# 04_-_MICRO.net
KiCad netlist of a schematic drawn in Altium Designer
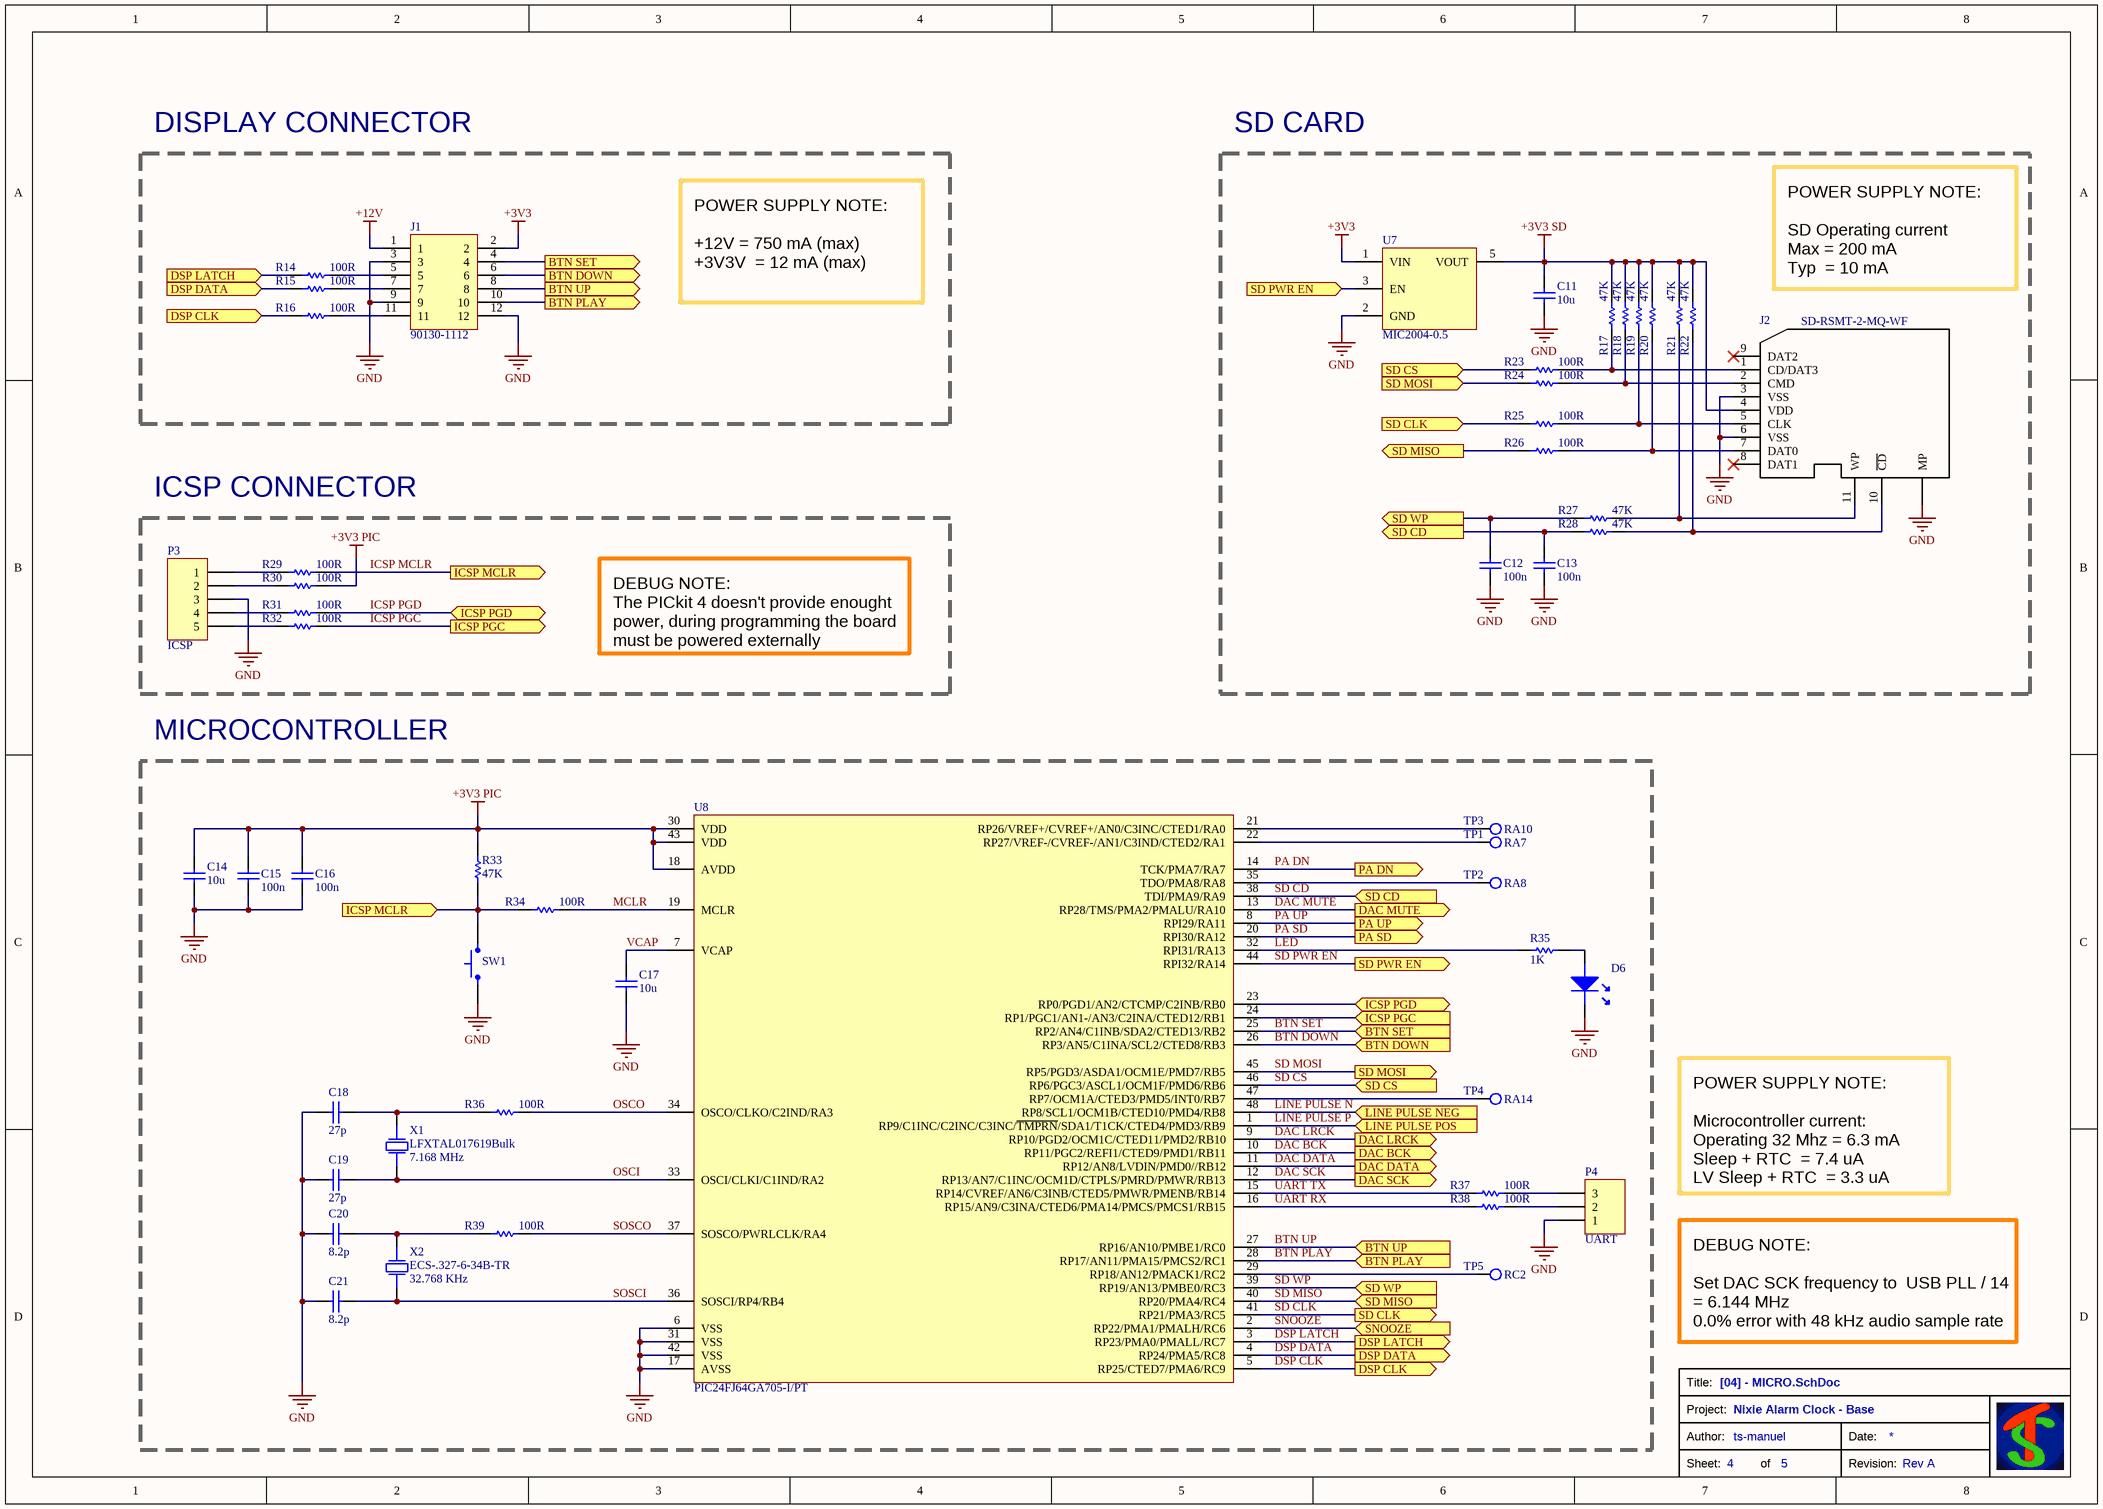
[diagram p0: [04] - MICRO.SchDoc]

(export (version "E")
  (design (tool "Eeschema 10.0.6"))
  (components
    (comp (ref "C11")
      (value "10u")
      (footprint "CAP-0805")
      (description "MLCC - SMD 25V 10uF X5R 10%")
      (fields (field (name "MANUFACTURER") "Samsung") (field (name "TOLERANCE") "10%"))
      (libsource (lib "Passives") (part "CAP-0805-10u-25V-X5R-10%"))
    )
    (comp (ref "C12")
      (value "100n")
      (footprint "CAP-0603")
      (description "MLCC - SMD 16V 100nF X7R 0603 20%")
      (fields (field (name "TOLERANCE") "20%") (field (name "MANUFACTURER") "KEMET"))
      (libsource (lib "Passives") (part "CAP-0603-100n-16V-X7R-20%"))
    )
    (comp (ref "C13")
      (value "100n")
      (footprint "CAP-0603")
      (description "MLCC - SMD 16V 100nF X7R 0603 20%")
      (fields (field (name "TOLERANCE") "20%") (field (name "MANUFACTURER") "KEMET"))
      (libsource (lib "Passives") (part "CAP-0603-100n-16V-X7R-20%"))
    )
    (comp (ref "C14")
      (value "10u")
      (footprint "CAP-0805")
      (description "MLCC - SMD 25V 10uF X5R 10%")
      (fields (field (name "MANUFACTURER") "Samsung") (field (name "TOLERANCE") "10%"))
      (libsource (lib "Passives") (part "CAP-0805-10u-25V-X5R-10%"))
    )
    (comp (ref "C15")
      (value "100n")
      (footprint "CAP-0603")
      (description "MLCC - SMD 16V 100nF X7R 0603 20%")
      (fields (field (name "TOLERANCE") "20%") (field (name "MANUFACTURER") "KEMET"))
      (libsource (lib "Passives") (part "CAP-0603-100n-16V-X7R-20%"))
    )
    (comp (ref "C16")
      (value "100n")
      (footprint "CAP-0603")
      (description "MLCC - SMD 16V 100nF X7R 0603 20%")
      (fields (field (name "TOLERANCE") "20%") (field (name "MANUFACTURER") "KEMET"))
      (libsource (lib "Passives") (part "CAP-0603-100n-16V-X7R-20%"))
    )
    (comp (ref "C17")
      (value "10u")
      (footprint "CAP-0805")
      (description "MLCC - SMD 25V 10uF X5R 10%")
      (fields (field (name "MANUFACTURER") "Samsung") (field (name "TOLERANCE") "10%"))
      (libsource (lib "Passives") (part "CAP-0805-10u-25V-X5R-10%"))
    )
    (comp (ref "C18")
      (value "27p")
      (footprint "CAP-0603")
      (description "MLCC - SMD 50V 27pF NP0 0603 5%")
      (fields (field (name "MANUFACTURER") "KEMET") (field (name "TOLERANCE") "5%"))
      (libsource (lib "Passives") (part "CAP-0603-27p-50V-NP0-5%"))
    )
    (comp (ref "C19")
      (value "27p")
      (footprint "CAP-0603")
      (description "MLCC - SMD 50V 27pF NP0 0603 5%")
      (fields (field (name "MANUFACTURER") "KEMET") (field (name "TOLERANCE") "5%"))
      (libsource (lib "Passives") (part "CAP-0603-27p-50V-NP0-5%"))
    )
    (comp (ref "C20")
      (value "8.2p")
      (footprint "CAP-0603")
      (description "MLCC - SMD 50V 8.2pF NP0 0603 5%")
      (fields (field (name "MANUFACTURER") "YAGEO") (field (name "TOLERANCE") "5%"))
      (libsource (lib "Passives") (part "CAP-0603-8p2-50V-NP0-5%"))
    )
    (comp (ref "C21")
      (value "8.2p")
      (footprint "CAP-0603")
      (description "MLCC - SMD 50V 8.2pF NP0 0603 5%")
      (fields (field (name "MANUFACTURER") "YAGEO") (field (name "TOLERANCE") "5%"))
      (libsource (lib "Passives") (part "CAP-0603-8p2-50V-NP0-5%"))
    )
    (comp (ref "D6")
      (value "150060VS75000")
      (footprint "LED-SMD-0603-1.6X0.8")
      (description "Standard LEDs - SMD WL-SMCW SMDMono TpVw Waterclr 0603 BrtGrn")
      (fields (field (name "MANUFACTURER") "Wurth Elektronik"))
      (libsource (lib "mt_local_library") (part "LED-SMD-0603-Green-150060VS75000"))
    )
    (comp (ref "J1")
      (value "90130-1112")
      (footprint "SHDR12W65P254_2X6_1758X975X1110P")
      (description "Terminali e capicorda 2.54MM CGRIDIII HDR 12P V DR SHRD TIN")
      (libsource (lib "mt_local_library") (part "HEADER-12x2-2.54-TH-90130-1112"))
    )
    (comp (ref "J2")
      (value "SD-RSMT-2-MQ-WF")
      (footprint "SD 3M SD-RSMT-2-MQ-WF")
      (description "Connettori per schede di memoria SD CARD CONNECTOR")
      (libsource (lib "mt_local_library") (part "SD-PUSH-PUSH-SD-RSMT-2-MQ-WF"))
    )
    (comp (ref "P3")
      (value "ICSP")
      (footprint "HDR1X5")
      (description "Header, 5-Pin")
      (fields (field (name "PUBLISHER") "Altium Limited"))
      (libsource (lib "Miscellaneous Connectors") (part "Header 5"))
    )
    (comp (ref "P4")
      (value "UART")
      (footprint "HDR1X3")
      (description "Header, 3-Pin")
      (fields (field (name "PUBLISHER") "Altium Limited"))
      (libsource (lib "Miscellaneous Connectors") (part "Header 3"))
    )
    (comp (ref "R14")
      (value "100R")
      (footprint "RES-0603")
      (description "Thick Film - SMD 75V 1/10W 100 ohm 0603 1%")
      (fields (field (name "MANUFACTURER") "Yageo") (field (name "TOLERANCE") "1%"))
      (libsource (lib "Passives") (part "RES-0603-100R-1/10W-1%"))
    )
    (comp (ref "R15")
      (value "100R")
      (footprint "RES-0603")
      (description "Thick Film - SMD 75V 1/10W 100 ohm 0603 1%")
      (fields (field (name "MANUFACTURER") "Yageo") (field (name "TOLERANCE") "1%"))
      (libsource (lib "Passives") (part "RES-0603-100R-1/10W-1%"))
    )
    (comp (ref "R16")
      (value "100R")
      (footprint "RES-0603")
      (description "Thick Film - SMD 75V 1/10W 100 ohm 0603 1%")
      (fields (field (name "MANUFACTURER") "Yageo") (field (name "TOLERANCE") "1%"))
      (libsource (lib "Passives") (part "RES-0603-100R-1/10W-1%"))
    )
    (comp (ref "R17")
      (value "47K")
      (footprint "RES-0603")
      (description "Thick Film - SMD 75V 1/10W 47K ohm 0603 1%")
      (fields (field (name "MANUFACTURER") "Yageo") (field (name "TOLERANCE") "1%"))
      (libsource (lib "Passives") (part "RES-0603-47K-1/10W-1%"))
    )
    (comp (ref "R18")
      (value "47K")
      (footprint "RES-0603")
      (description "Thick Film - SMD 75V 1/10W 47K ohm 0603 1%")
      (fields (field (name "MANUFACTURER") "Yageo") (field (name "TOLERANCE") "1%"))
      (libsource (lib "Passives") (part "RES-0603-47K-1/10W-1%"))
    )
    (comp (ref "R19")
      (value "47K")
      (footprint "RES-0603")
      (description "Thick Film - SMD 75V 1/10W 47K ohm 0603 1%")
      (fields (field (name "MANUFACTURER") "Yageo") (field (name "TOLERANCE") "1%"))
      (libsource (lib "Passives") (part "RES-0603-47K-1/10W-1%"))
    )
    (comp (ref "R20")
      (value "47K")
      (footprint "RES-0603")
      (description "Thick Film - SMD 75V 1/10W 47K ohm 0603 1%")
      (fields (field (name "MANUFACTURER") "Yageo") (field (name "TOLERANCE") "1%"))
      (libsource (lib "Passives") (part "RES-0603-47K-1/10W-1%"))
    )
    (comp (ref "R21")
      (value "47K")
      (footprint "RES-0603")
      (description "Thick Film - SMD 75V 1/10W 47K ohm 0603 1%")
      (fields (field (name "MANUFACTURER") "Yageo") (field (name "TOLERANCE") "1%"))
      (libsource (lib "Passives") (part "RES-0603-47K-1/10W-1%"))
    )
    (comp (ref "R22")
      (value "47K")
      (footprint "RES-0603")
      (description "Thick Film - SMD 75V 1/10W 47K ohm 0603 1%")
      (fields (field (name "MANUFACTURER") "Yageo") (field (name "TOLERANCE") "1%"))
      (libsource (lib "Passives") (part "RES-0603-47K-1/10W-1%"))
    )
    (comp (ref "R23")
      (value "100R")
      (footprint "RES-0603")
      (description "Thick Film - SMD 75V 1/10W 100 ohm 0603 1%")
      (fields (field (name "MANUFACTURER") "Yageo") (field (name "TOLERANCE") "1%"))
      (libsource (lib "Passives") (part "RES-0603-100R-1/10W-1%"))
    )
    (comp (ref "R24")
      (value "100R")
      (footprint "RES-0603")
      (description "Thick Film - SMD 75V 1/10W 100 ohm 0603 1%")
      (fields (field (name "MANUFACTURER") "Yageo") (field (name "TOLERANCE") "1%"))
      (libsource (lib "Passives") (part "RES-0603-100R-1/10W-1%"))
    )
    (comp (ref "R25")
      (value "100R")
      (footprint "RES-0603")
      (description "Thick Film - SMD 75V 1/10W 100 ohm 0603 1%")
      (fields (field (name "MANUFACTURER") "Yageo") (field (name "TOLERANCE") "1%"))
      (libsource (lib "Passives") (part "RES-0603-100R-1/10W-1%"))
    )
    (comp (ref "R26")
      (value "100R")
      (footprint "RES-0603")
      (description "Thick Film - SMD 75V 1/10W 100 ohm 0603 1%")
      (fields (field (name "MANUFACTURER") "Yageo") (field (name "TOLERANCE") "1%"))
      (libsource (lib "Passives") (part "RES-0603-100R-1/10W-1%"))
    )
    (comp (ref "R27")
      (value "47K")
      (footprint "RES-0603")
      (description "Thick Film - SMD 75V 1/10W 47K ohm 0603 1%")
      (fields (field (name "MANUFACTURER") "Yageo") (field (name "TOLERANCE") "1%"))
      (libsource (lib "Passives") (part "RES-0603-47K-1/10W-1%"))
    )
    (comp (ref "R28")
      (value "47K")
      (footprint "RES-0603")
      (description "Thick Film - SMD 75V 1/10W 47K ohm 0603 1%")
      (fields (field (name "MANUFACTURER") "Yageo") (field (name "TOLERANCE") "1%"))
      (libsource (lib "Passives") (part "RES-0603-47K-1/10W-1%"))
    )
    (comp (ref "R29")
      (value "100R")
      (footprint "RES-0603")
      (description "Thick Film - SMD 75V 1/10W 100 ohm 0603 1%")
      (fields (field (name "MANUFACTURER") "Yageo") (field (name "TOLERANCE") "1%"))
      (libsource (lib "Passives") (part "RES-0603-100R-1/10W-1%"))
    )
    (comp (ref "R30")
      (value "100R")
      (footprint "RES-0603")
      (description "Thick Film - SMD 75V 1/10W 100 ohm 0603 1%")
      (fields (field (name "MANUFACTURER") "Yageo") (field (name "TOLERANCE") "1%"))
      (libsource (lib "Passives") (part "RES-0603-100R-1/10W-1%"))
    )
    (comp (ref "R31")
      (value "100R")
      (footprint "RES-0603")
      (description "Thick Film - SMD 75V 1/10W 100 ohm 0603 1%")
      (fields (field (name "MANUFACTURER") "Yageo") (field (name "TOLERANCE") "1%"))
      (libsource (lib "Passives") (part "RES-0603-100R-1/10W-1%"))
    )
    (comp (ref "R32")
      (value "100R")
      (footprint "RES-0603")
      (description "Thick Film - SMD 75V 1/10W 100 ohm 0603 1%")
      (fields (field (name "MANUFACTURER") "Yageo") (field (name "TOLERANCE") "1%"))
      (libsource (lib "Passives") (part "RES-0603-100R-1/10W-1%"))
    )
    (comp (ref "R33")
      (value "47K")
      (footprint "RES-0603")
      (description "Thick Film - SMD 75V 1/10W 47K ohm 0603 1%")
      (fields (field (name "MANUFACTURER") "Yageo") (field (name "TOLERANCE") "1%"))
      (libsource (lib "Passives") (part "RES-0603-47K-1/10W-1%"))
    )
    (comp (ref "R34")
      (value "100R")
      (footprint "RES-0603")
      (description "Thick Film - SMD 75V 1/10W 100 ohm 0603 1%")
      (fields (field (name "MANUFACTURER") "Yageo") (field (name "TOLERANCE") "1%"))
      (libsource (lib "Passives") (part "RES-0603-100R-1/10W-1%"))
    )
    (comp (ref "R35")
      (value "1K")
      (footprint "RES-0603")
      (description "Thick Film - SMD 75V 1/10W 1K ohm 0603 1%")
      (fields (field (name "MANUFACTURER") "Yageo") (field (name "TOLERANCE") "1%"))
      (libsource (lib "Passives") (part "RES-0603-1K-1/10W-1%"))
    )
    (comp (ref "R36")
      (value "100R")
      (footprint "RES-0603")
      (description "Thick Film - SMD 75V 1/10W 100 ohm 0603 1%")
      (fields (field (name "MANUFACTURER") "Yageo") (field (name "TOLERANCE") "1%"))
      (libsource (lib "Passives") (part "RES-0603-100R-1/10W-1%"))
    )
    (comp (ref "R37")
      (value "100R")
      (footprint "RES-0603")
      (description "Thick Film - SMD 75V 1/10W 100 ohm 0603 1%")
      (fields (field (name "MANUFACTURER") "Yageo") (field (name "TOLERANCE") "1%"))
      (libsource (lib "Passives") (part "RES-0603-100R-1/10W-1%"))
    )
    (comp (ref "R38")
      (value "100R")
      (footprint "RES-0603")
      (description "Thick Film - SMD 75V 1/10W 100 ohm 0603 1%")
      (fields (field (name "MANUFACTURER") "Yageo") (field (name "TOLERANCE") "1%"))
      (libsource (lib "Passives") (part "RES-0603-100R-1/10W-1%"))
    )
    (comp (ref "R39")
      (value "100R")
      (footprint "RES-0603")
      (description "Thick Film - SMD 75V 1/10W 100 ohm 0603 1%")
      (fields (field (name "MANUFACTURER") "Yageo") (field (name "TOLERANCE") "1%"))
      (libsource (lib "Passives") (part "RES-0603-100R-1/10W-1%"))
    )
    (comp (ref "SW1")
      (value "Push Button 6mm TH")
      (footprint "Push Button 6mm TH")
      (libsource (lib "mt_local_library") (part "Push Button 6mm TH"))
    )
    (comp (ref "TP1")
      (value "RA7")
      (footprint "TESTPOINT-1mm")
      (libsource (lib "mt_local_library") (part "TESTPOINT-SMD-1mm"))
    )
    (comp (ref "TP2")
      (value "RA8")
      (footprint "TESTPOINT-1mm")
      (libsource (lib "mt_local_library") (part "TESTPOINT-SMD-1mm"))
    )
    (comp (ref "TP3")
      (value "RA10")
      (footprint "TESTPOINT-1mm")
      (libsource (lib "mt_local_library") (part "TESTPOINT-SMD-1mm"))
    )
    (comp (ref "TP4")
      (value "RA14")
      (footprint "TESTPOINT-1mm")
      (libsource (lib "mt_local_library") (part "TESTPOINT-SMD-1mm"))
    )
    (comp (ref "TP5")
      (value "RC2")
      (footprint "TESTPOINT-1mm")
      (libsource (lib "mt_local_library") (part "TESTPOINT-SMD-1mm"))
    )
    (comp (ref "U7")
      (value "MIC2004-0.5")
      (footprint "SOT23-5")
      (description "Fixed 0.5A Current Limiting Power Distribution Switches")
      (libsource (lib "mt_local_library") (part "MIC2004-0.5"))
    )
    (comp (ref "U8")
      (value "PIC24FJ64GA705-I/PT")
      (footprint "TSQFP50P900X900X120-48N")
      (description "Microcontrollori a 16 bit - MCU 16-bit, 16 MIPS, 64KB Flash, 16KB RAM")
      (libsource (lib "mt_local_library") (part "PIC24FJ64GA705"))
    )
    (comp (ref "X1")
      (value "LFXTAL017619Bulk")
      (footprint "XTAL1140X490X430_HC49")
      (description "Crystal 7.168MHz 20ppm 30pF -10C +60C")
      (fields (field (name "ALTIUM_VALUE") "7.168 MHz"))
      (libsource (lib "mt_local_library") (part "XTAL-SMD-7.168MHz"))
    )
    (comp (ref "X2")
      (value "ECS-.327-6-34B-TR")
      (footprint "XTAL-ECS-3.2 mm x 1.5 mm")
      (description "Crystal 32.768kHz 20ppm 6pF -40C +85C")
      (fields (field (name "ALTIUM_VALUE") "32.768 KHz"))
      (libsource (lib "mt_local_library") (part "XTAL-32.768KHz-ECS-.327-6-34B-TR"))
    )
  )
  (nets
    (net (code "1") (name "+3V3") (class "Default")
      (node (ref "J1") (pin "2") (pinfunction "2_2") (pintype "passive"))
      (node (ref "U7") (pin "1") (pinfunction "VIN_1") (pintype "power_in"))
    )
    (net (code "2") (name "+3V3 PIC") (class "Default")
      (node (ref "C14") (pin "1") (pinfunction "1_1") (pintype "passive"))
      (node (ref "C15") (pin "2") (pinfunction "2_2") (pintype "passive"))
      (node (ref "C16") (pin "2") (pinfunction "2_2") (pintype "passive"))
      (node (ref "R30") (pin "2") (pinfunction "2_2") (pintype "passive"))
      (node (ref "R33") (pin "2") (pinfunction "2_2") (pintype "passive"))
      (node (ref "U8") (pin "18") (pinfunction "AVDD_18") (pintype "passive"))
      (node (ref "U8") (pin "30") (pinfunction "VDD_30") (pintype "passive"))
      (node (ref "U8") (pin "43") (pinfunction "VDD_43") (pintype "passive"))
    )
    (net (code "3") (name "+3V3 SD") (class "Default")
      (node (ref "C11") (pin "1") (pinfunction "1_1") (pintype "passive"))
      (node (ref "J2") (pin "4") (pinfunction "VDD_4") (pintype "power_in"))
      (node (ref "R17") (pin "2") (pinfunction "2_2") (pintype "passive"))
      (node (ref "R18") (pin "2") (pinfunction "2_2") (pintype "passive"))
      (node (ref "R19") (pin "2") (pinfunction "2_2") (pintype "passive"))
      (node (ref "R20") (pin "2") (pinfunction "2_2") (pintype "passive"))
      (node (ref "R21") (pin "2") (pinfunction "2_2") (pintype "passive"))
      (node (ref "R22") (pin "2") (pinfunction "2_2") (pintype "passive"))
      (node (ref "U7") (pin "5") (pinfunction "VOUT_5") (pintype "power_in"))
    )
    (net (code "4") (name "+12V") (class "Default")
      (node (ref "J1") (pin "1") (pinfunction "1_1") (pintype "passive"))
    )
    (net (code "5") (name "/BTN DOWN") (class "Default")
      (node (ref "J1") (pin "6") (pinfunction "6_6") (pintype "passive"))
      (node (ref "U8") (pin "26") (pinfunction "RP3/AN5/C1INA/SCL2/CTED8/RB3_26") (pintype "passive"))
    )
    (net (code "6") (name "/BTN PLAY") (class "Default")
      (node (ref "J1") (pin "10") (pinfunction "10_10") (pintype "passive"))
      (node (ref "U8") (pin "28") (pinfunction "RP17/AN11/PMA15/PMCS2/RC1_28") (pintype "passive"))
    )
    (net (code "7") (name "/BTN SET") (class "Default")
      (node (ref "J1") (pin "4") (pinfunction "4_4") (pintype "passive"))
      (node (ref "U8") (pin "25") (pinfunction "RP2/AN4/C1INB/SDA2/CTED13/RB2_25") (pintype "passive"))
    )
    (net (code "8") (name "/BTN UP") (class "Default")
      (node (ref "J1") (pin "8") (pinfunction "8_8") (pintype "passive"))
      (node (ref "U8") (pin "27") (pinfunction "RP16/AN10/PMBE1/RC0_27") (pintype "passive"))
    )
    (net (code "9") (name "/DAC BCK") (class "Default")
      (node (ref "U8") (pin "10") (pinfunction "RP11/PGC2/REFI1/CTED9/PMD1/RB11_10") (pintype "passive"))
    )
    (net (code "10") (name "/DAC DATA") (class "Default")
      (node (ref "U8") (pin "11") (pinfunction "RP12/AN8/LVDIN/PMD0//RB12_11") (pintype "passive"))
    )
    (net (code "11") (name "/DAC LRCK") (class "Default")
      (node (ref "U8") (pin "9") (pinfunction "RP10/PGD2/OCM1C/CTED11/PMD2/RB10_9") (pintype "passive"))
    )
    (net (code "12") (name "/DAC MUTE") (class "Default")
      (node (ref "U8") (pin "13") (pinfunction "RP28/TMS/PMA2/PMALU/RA10_13") (pintype "passive"))
    )
    (net (code "13") (name "/DAC SCK") (class "Default")
      (node (ref "U8") (pin "12") (pinfunction "RP13/AN7/C1INC/OCM1D/CTPLS/PMRD/PMWR/RB13_12") (pintype "passive"))
    )
    (net (code "14") (name "/DSP CLK") (class "Default")
      (node (ref "R16") (pin "1") (pinfunction "1_1") (pintype "passive"))
      (node (ref "U8") (pin "5") (pinfunction "RP25/CTED7/PMA6/RC9_5") (pintype "passive"))
    )
    (net (code "15") (name "/DSP DATA") (class "Default")
      (node (ref "R15") (pin "1") (pinfunction "1_1") (pintype "passive"))
      (node (ref "U8") (pin "4") (pinfunction "RP24/PMA5/RC8_4") (pintype "passive"))
    )
    (net (code "16") (name "/DSP LATCH") (class "Default")
      (node (ref "R14") (pin "1") (pinfunction "1_1") (pintype "passive"))
      (node (ref "U8") (pin "3") (pinfunction "RP23/PMA0/PMALL/RC7_3") (pintype "passive"))
    )
    (net (code "17") (name "/ICSP MCLR") (class "Default")
      (node (ref "R29") (pin "2") (pinfunction "2_2") (pintype "passive"))
      (node (ref "R33") (pin "1") (pinfunction "1_1") (pintype "passive"))
      (node (ref "R34") (pin "1") (pinfunction "1_1") (pintype "passive"))
      (node (ref "SW1") (pin "2") (pinfunction "2_2") (pintype "passive"))
    )
    (net (code "18") (name "/ICSP PGC") (class "Default")
      (node (ref "R32") (pin "2") (pinfunction "2_2") (pintype "passive"))
      (node (ref "U8") (pin "24") (pinfunction "RP1/PGC1/AN1-/AN3/C2INA/CTED12/RB1_24") (pintype "passive"))
    )
    (net (code "19") (name "/ICSP PGD") (class "Default")
      (node (ref "R31") (pin "2") (pinfunction "2_2") (pintype "passive"))
      (node (ref "U8") (pin "23") (pinfunction "RP0/PGD1/AN2/CTCMP/C2INB/RB0_23") (pintype "passive"))
    )
    (net (code "20") (name "/LED") (class "Default")
      (node (ref "R35") (pin "1") (pinfunction "1_1") (pintype "passive"))
      (node (ref "U8") (pin "32") (pinfunction "RPI31/RA13_32") (pintype "passive"))
    )
    (net (code "21") (name "/LINE PULSE N") (class "Default")
      (node (ref "U8") (pin "48") (pinfunction "RP8/SCL1/OCM1B/CTED10/PMD4/RB8_48") (pintype "passive"))
    )
    (net (code "22") (name "/LINE PULSE P") (class "Default")
      (node (ref "U8") (pin "1") (pinfunction "RP9/C1INC/C2INC/C3INC/~{TMPRN}/SDA1/T1CK/CTED4/PMD3/RB9_1") (pintype "passive"))
    )
    (net (code "23") (name "/MCLR") (class "Default")
      (node (ref "R34") (pin "2") (pinfunction "2_2") (pintype "passive"))
      (node (ref "U8") (pin "19") (pinfunction "MCLR_19") (pintype "passive"))
    )
    (net (code "24") (name "/OSCI") (class "Default")
      (node (ref "C19") (pin "1") (pinfunction "1_1") (pintype "passive"))
      (node (ref "U8") (pin "33") (pinfunction "OSCI/CLKI/C1IND/RA2_33") (pintype "passive"))
      (node (ref "X1") (pin "1") (pinfunction "1_1") (pintype "passive"))
    )
    (net (code "25") (name "/OSCO") (class "Default")
      (node (ref "R36") (pin "2") (pinfunction "2_2") (pintype "passive"))
      (node (ref "U8") (pin "34") (pinfunction "OSCO/CLKO/C2IND/RA3_34") (pintype "passive"))
    )
    (net (code "26") (name "/PA DN") (class "Default")
      (node (ref "U8") (pin "14") (pinfunction "TCK/PMA7/RA7_14") (pintype "passive"))
    )
    (net (code "27") (name "/PA SD") (class "Default")
      (node (ref "U8") (pin "20") (pinfunction "RPI30/RA12_20") (pintype "passive"))
    )
    (net (code "28") (name "/PA UP") (class "Default")
      (node (ref "U8") (pin "8") (pinfunction "RPI29/RA11_8") (pintype "passive"))
    )
    (net (code "29") (name "/SD CD") (class "Default")
      (node (ref "C13") (pin "2") (pinfunction "2_2") (pintype "passive"))
      (node (ref "R28") (pin "1") (pinfunction "1_1") (pintype "passive"))
      (node (ref "U8") (pin "38") (pinfunction "TDI/PMA9/RA9_38") (pintype "passive"))
    )
    (net (code "30") (name "/SD CLK") (class "Default")
      (node (ref "R25") (pin "1") (pinfunction "1_1") (pintype "passive"))
      (node (ref "U8") (pin "41") (pinfunction "RP21/PMA3/RC5_41") (pintype "passive"))
    )
    (net (code "31") (name "/SD CS") (class "Default")
      (node (ref "R23") (pin "1") (pinfunction "1_1") (pintype "passive"))
      (node (ref "U8") (pin "46") (pinfunction "RP6/PGC3/ASCL1/OCM1F/PMD6/RB6_46") (pintype "passive"))
    )
    (net (code "32") (name "/SD MISO") (class "Default")
      (node (ref "R26") (pin "1") (pinfunction "1_1") (pintype "passive"))
      (node (ref "U8") (pin "40") (pinfunction "RP20/PMA4/RC4_40") (pintype "passive"))
    )
    (net (code "33") (name "/SD MOSI") (class "Default")
      (node (ref "R24") (pin "1") (pinfunction "1_1") (pintype "passive"))
      (node (ref "U8") (pin "45") (pinfunction "RP5/PGD3/ASDA1/OCM1E/PMD7/RB5_45") (pintype "passive"))
    )
    (net (code "34") (name "/SD PWR EN") (class "Default")
      (node (ref "U7") (pin "3") (pinfunction "EN_3") (pintype "passive"))
      (node (ref "U8") (pin "44") (pinfunction "RPI32/RA14_44") (pintype "passive"))
    )
    (net (code "35") (name "/SD WP") (class "Default")
      (node (ref "C12") (pin "2") (pinfunction "2_2") (pintype "passive"))
      (node (ref "R27") (pin "1") (pinfunction "1_1") (pintype "passive"))
      (node (ref "U8") (pin "39") (pinfunction "RP19/AN13/PMBE0/RC3_39") (pintype "passive"))
    )
    (net (code "36") (name "/SNOOZE") (class "Default")
      (node (ref "U8") (pin "2") (pinfunction "RP22/PMA1/PMALH/RC6_2") (pintype "passive"))
    )
    (net (code "37") (name "/SOSCI") (class "Default")
      (node (ref "C21") (pin "1") (pinfunction "1_1") (pintype "passive"))
      (node (ref "U8") (pin "36") (pinfunction "SOSCI/RP4/RB4_36") (pintype "passive"))
      (node (ref "X2") (pin "1") (pinfunction "1_1") (pintype "passive"))
    )
    (net (code "38") (name "/SOSCO") (class "Default")
      (node (ref "R39") (pin "2") (pinfunction "2_2") (pintype "passive"))
      (node (ref "U8") (pin "37") (pinfunction "SOSCO/PWRLCLK/RA4_37") (pintype "passive"))
    )
    (net (code "39") (name "/UART RX") (class "Default")
      (node (ref "R38") (pin "1") (pinfunction "1_1") (pintype "passive"))
      (node (ref "U8") (pin "16") (pinfunction "RP15/AN9/C3INA/CTED6/PMA14/PMCS/PMCS1/RB15_16") (pintype "passive"))
    )
    (net (code "40") (name "/UART TX") (class "Default")
      (node (ref "R37") (pin "1") (pinfunction "1_1") (pintype "passive"))
      (node (ref "U8") (pin "15") (pinfunction "RP14/CVREF/AN6/C3INB/CTED5/PMWR/PMENB/RB14_15") (pintype "passive"))
    )
    (net (code "41") (name "/VCAP") (class "Default")
      (node (ref "C17") (pin "1") (pinfunction "1_1") (pintype "passive"))
      (node (ref "U8") (pin "7") (pinfunction "VCAP_7") (pintype "passive"))
    )
    (net (code "42") (name "GND") (class "Default")
      (node (ref "C11") (pin "2") (pinfunction "2_2") (pintype "passive"))
      (node (ref "C12") (pin "1") (pinfunction "1_1") (pintype "passive"))
      (node (ref "C13") (pin "1") (pinfunction "1_1") (pintype "passive"))
      (node (ref "C14") (pin "2") (pinfunction "2_2") (pintype "passive"))
      (node (ref "C15") (pin "1") (pinfunction "1_1") (pintype "passive"))
      (node (ref "C16") (pin "1") (pinfunction "1_1") (pintype "passive"))
      (node (ref "C17") (pin "2") (pinfunction "2_2") (pintype "passive"))
      (node (ref "C18") (pin "2") (pinfunction "2_2") (pintype "passive"))
      (node (ref "C19") (pin "2") (pinfunction "2_2") (pintype "passive"))
      (node (ref "C20") (pin "2") (pinfunction "2_2") (pintype "passive"))
      (node (ref "C21") (pin "2") (pinfunction "2_2") (pintype "passive"))
      (node (ref "D6") (pin "K") (pinfunction "K_K") (pintype "passive"))
      (node (ref "J1") (pin "12") (pinfunction "12_12") (pintype "passive"))
      (node (ref "J1") (pin "3") (pinfunction "3_3") (pintype "passive"))
      (node (ref "J1") (pin "9") (pinfunction "9_9") (pintype "passive"))
      (node (ref "J2") (pin "3") (pinfunction "VSS_3") (pintype "power_in"))
      (node (ref "J2") (pin "6") (pinfunction "VSS_6") (pintype "power_in"))
      (node (ref "J2") (pin "MP") (pinfunction "MP_MP") (pintype "passive"))
      (node (ref "P3") (pin "3") (pinfunction "3_3") (pintype "passive"))
      (node (ref "P4") (pin "1") (pinfunction "1_1") (pintype "passive"))
      (node (ref "SW1") (pin "1") (pinfunction "1_1") (pintype "passive"))
      (node (ref "U7") (pin "2") (pinfunction "GND_2") (pintype "power_in"))
      (node (ref "U8") (pin "17") (pinfunction "AVSS_17") (pintype "passive"))
      (node (ref "U8") (pin "31") (pinfunction "VSS_31") (pintype "passive"))
      (node (ref "U8") (pin "42") (pinfunction "VSS_42") (pintype "passive"))
      (node (ref "U8") (pin "6") (pinfunction "VSS_6") (pintype "passive"))
    )
    (net (code "43") (name "Net-(C18-Pad1)") (class "Default")
      (node (ref "C18") (pin "1") (pinfunction "1_1") (pintype "passive"))
      (node (ref "R36") (pin "1") (pinfunction "1_1") (pintype "passive"))
      (node (ref "X1") (pin "2") (pinfunction "2_2") (pintype "passive"))
    )
    (net (code "44") (name "Net-(C20-Pad1)") (class "Default")
      (node (ref "C20") (pin "1") (pinfunction "1_1") (pintype "passive"))
      (node (ref "R39") (pin "1") (pinfunction "1_1") (pintype "passive"))
      (node (ref "X2") (pin "2") (pinfunction "2_2") (pintype "passive"))
    )
    (net (code "45") (name "Net-(D6-PadA)") (class "Default")
      (node (ref "D6") (pin "A") (pinfunction "A_A") (pintype "passive"))
      (node (ref "R35") (pin "2") (pinfunction "2_2") (pintype "passive"))
    )
    (net (code "46") (name "Net-(J1-Pad5)") (class "Default")
      (node (ref "J1") (pin "5") (pinfunction "5_5") (pintype "passive"))
      (node (ref "R14") (pin "2") (pinfunction "2_2") (pintype "passive"))
    )
    (net (code "47") (name "Net-(J1-Pad7)") (class "Default")
      (node (ref "J1") (pin "7") (pinfunction "7_7") (pintype "passive"))
      (node (ref "R15") (pin "2") (pinfunction "2_2") (pintype "passive"))
    )
    (net (code "48") (name "Net-(J1-Pad11)") (class "Default")
      (node (ref "J1") (pin "11") (pinfunction "11_11") (pintype "passive"))
      (node (ref "R16") (pin "2") (pinfunction "2_2") (pintype "passive"))
    )
    (net (code "49") (name "Net-(J2-CD{slash}DAT3)") (class "Default")
      (node (ref "J2") (pin "1") (pinfunction "CD/DAT3_1") (pintype "passive"))
      (node (ref "R17") (pin "1") (pinfunction "1_1") (pintype "passive"))
      (node (ref "R23") (pin "2") (pinfunction "2_2") (pintype "passive"))
    )
    (net (code "50") (name "Net-(J2-CLK)") (class "Default")
      (node (ref "J2") (pin "5") (pinfunction "CLK_5") (pintype "passive"))
      (node (ref "R19") (pin "1") (pinfunction "1_1") (pintype "passive"))
      (node (ref "R25") (pin "2") (pinfunction "2_2") (pintype "passive"))
    )
    (net (code "51") (name "Net-(J2-CMD)") (class "Default")
      (node (ref "J2") (pin "2") (pinfunction "CMD_2") (pintype "passive"))
      (node (ref "R18") (pin "1") (pinfunction "1_1") (pintype "passive"))
      (node (ref "R24") (pin "2") (pinfunction "2_2") (pintype "passive"))
    )
    (net (code "52") (name "Net-(J2-DAT0)") (class "Default")
      (node (ref "J2") (pin "7") (pinfunction "DAT0_7") (pintype "passive"))
      (node (ref "R20") (pin "1") (pinfunction "1_1") (pintype "passive"))
      (node (ref "R26") (pin "2") (pinfunction "2_2") (pintype "passive"))
    )
    (net (code "53") (name "Net-(J2-WP)") (class "Default")
      (node (ref "J2") (pin "11") (pinfunction "WP_11") (pintype "passive"))
      (node (ref "R21") (pin "1") (pinfunction "1_1") (pintype "passive"))
      (node (ref "R27") (pin "2") (pinfunction "2_2") (pintype "passive"))
    )
    (net (code "54") (name "Net-(J2-~{CD})") (class "Default")
      (node (ref "J2") (pin "10") (pinfunction "~{CD}_10") (pintype "passive"))
      (node (ref "R22") (pin "1") (pinfunction "1_1") (pintype "passive"))
      (node (ref "R28") (pin "2") (pinfunction "2_2") (pintype "passive"))
    )
    (net (code "55") (name "Net-(P3-Pad1)") (class "Default")
      (node (ref "P3") (pin "1") (pinfunction "1_1") (pintype "passive"))
      (node (ref "R29") (pin "1") (pinfunction "1_1") (pintype "passive"))
    )
    (net (code "56") (name "Net-(P3-Pad2)") (class "Default")
      (node (ref "P3") (pin "2") (pinfunction "2_2") (pintype "passive"))
      (node (ref "R30") (pin "1") (pinfunction "1_1") (pintype "passive"))
    )
    (net (code "57") (name "Net-(P3-Pad4)") (class "Default")
      (node (ref "P3") (pin "4") (pinfunction "4_4") (pintype "passive"))
      (node (ref "R31") (pin "1") (pinfunction "1_1") (pintype "passive"))
    )
    (net (code "58") (name "Net-(P3-Pad5)") (class "Default")
      (node (ref "P3") (pin "5") (pinfunction "5_5") (pintype "passive"))
      (node (ref "R32") (pin "1") (pinfunction "1_1") (pintype "passive"))
    )
    (net (code "59") (name "Net-(P4-Pad2)") (class "Default")
      (node (ref "P4") (pin "2") (pinfunction "2_2") (pintype "passive"))
      (node (ref "R38") (pin "2") (pinfunction "2_2") (pintype "passive"))
    )
    (net (code "60") (name "Net-(P4-Pad3)") (class "Default")
      (node (ref "P4") (pin "3") (pinfunction "3_3") (pintype "passive"))
      (node (ref "R37") (pin "2") (pinfunction "2_2") (pintype "passive"))
    )
    (net (code "61") (name "Net-(U8-RP7{slash}OCM1A{slash}CTED3{slash}PMD5{slash}INT0{slash}RB7)") (class "Default")
      (node (ref "TP4") (pin "1") (pinfunction "1_1") (pintype "passive"))
      (node (ref "U8") (pin "47") (pinfunction "RP7/OCM1A/CTED3/PMD5/INT0/RB7_47") (pintype "passive"))
    )
    (net (code "62") (name "Net-(U8-RP18{slash}AN12{slash}PMACK1{slash}RC2)") (class "Default")
      (node (ref "TP5") (pin "1") (pinfunction "1_1") (pintype "passive"))
      (node (ref "U8") (pin "29") (pinfunction "RP18/AN12/PMACK1/RC2_29") (pintype "passive"))
    )
    (net (code "63") (name "Net-(U8-RP26{slash}VREF+{slash}CVREF+{slash}AN0{slash}C3INC{slash}CTED1{slash}RA0)") (class "Default")
      (node (ref "TP3") (pin "1") (pinfunction "1_1") (pintype "passive"))
      (node (ref "U8") (pin "21") (pinfunction "RP26/VREF+/CVREF+/AN0/C3INC/CTED1/RA0_21") (pintype "passive"))
    )
    (net (code "64") (name "Net-(U8-RP27{slash}VREF-{slash}CVREF-{slash}AN1{slash}C3IND{slash}CTED2{slash}RA1)") (class "Default")
      (node (ref "TP1") (pin "1") (pinfunction "1_1") (pintype "passive"))
      (node (ref "U8") (pin "22") (pinfunction "RP27/VREF-/CVREF-/AN1/C3IND/CTED2/RA1_22") (pintype "passive"))
    )
    (net (code "65") (name "Net-(U8-TDO{slash}PMA8{slash}RA8)") (class "Default")
      (node (ref "TP2") (pin "1") (pinfunction "1_1") (pintype "passive"))
      (node (ref "U8") (pin "35") (pinfunction "TDO/PMA8/RA8_35") (pintype "passive"))
    )
    (net (code "66") (name "unconnected-(J2-DAT1-Pad8)") (class "Default")
      (node (ref "J2") (pin "8") (pinfunction "DAT1_8") (pintype "passive+no_connect"))
    )
    (net (code "67") (name "unconnected-(J2-DAT2-Pad9)") (class "Default")
      (node (ref "J2") (pin "9") (pinfunction "DAT2_9") (pintype "passive+no_connect"))
    )
  )
)
